# EDU_High-Speed-Design_MCU.net
KiCad netlist of a schematic drawn in Altium Designer
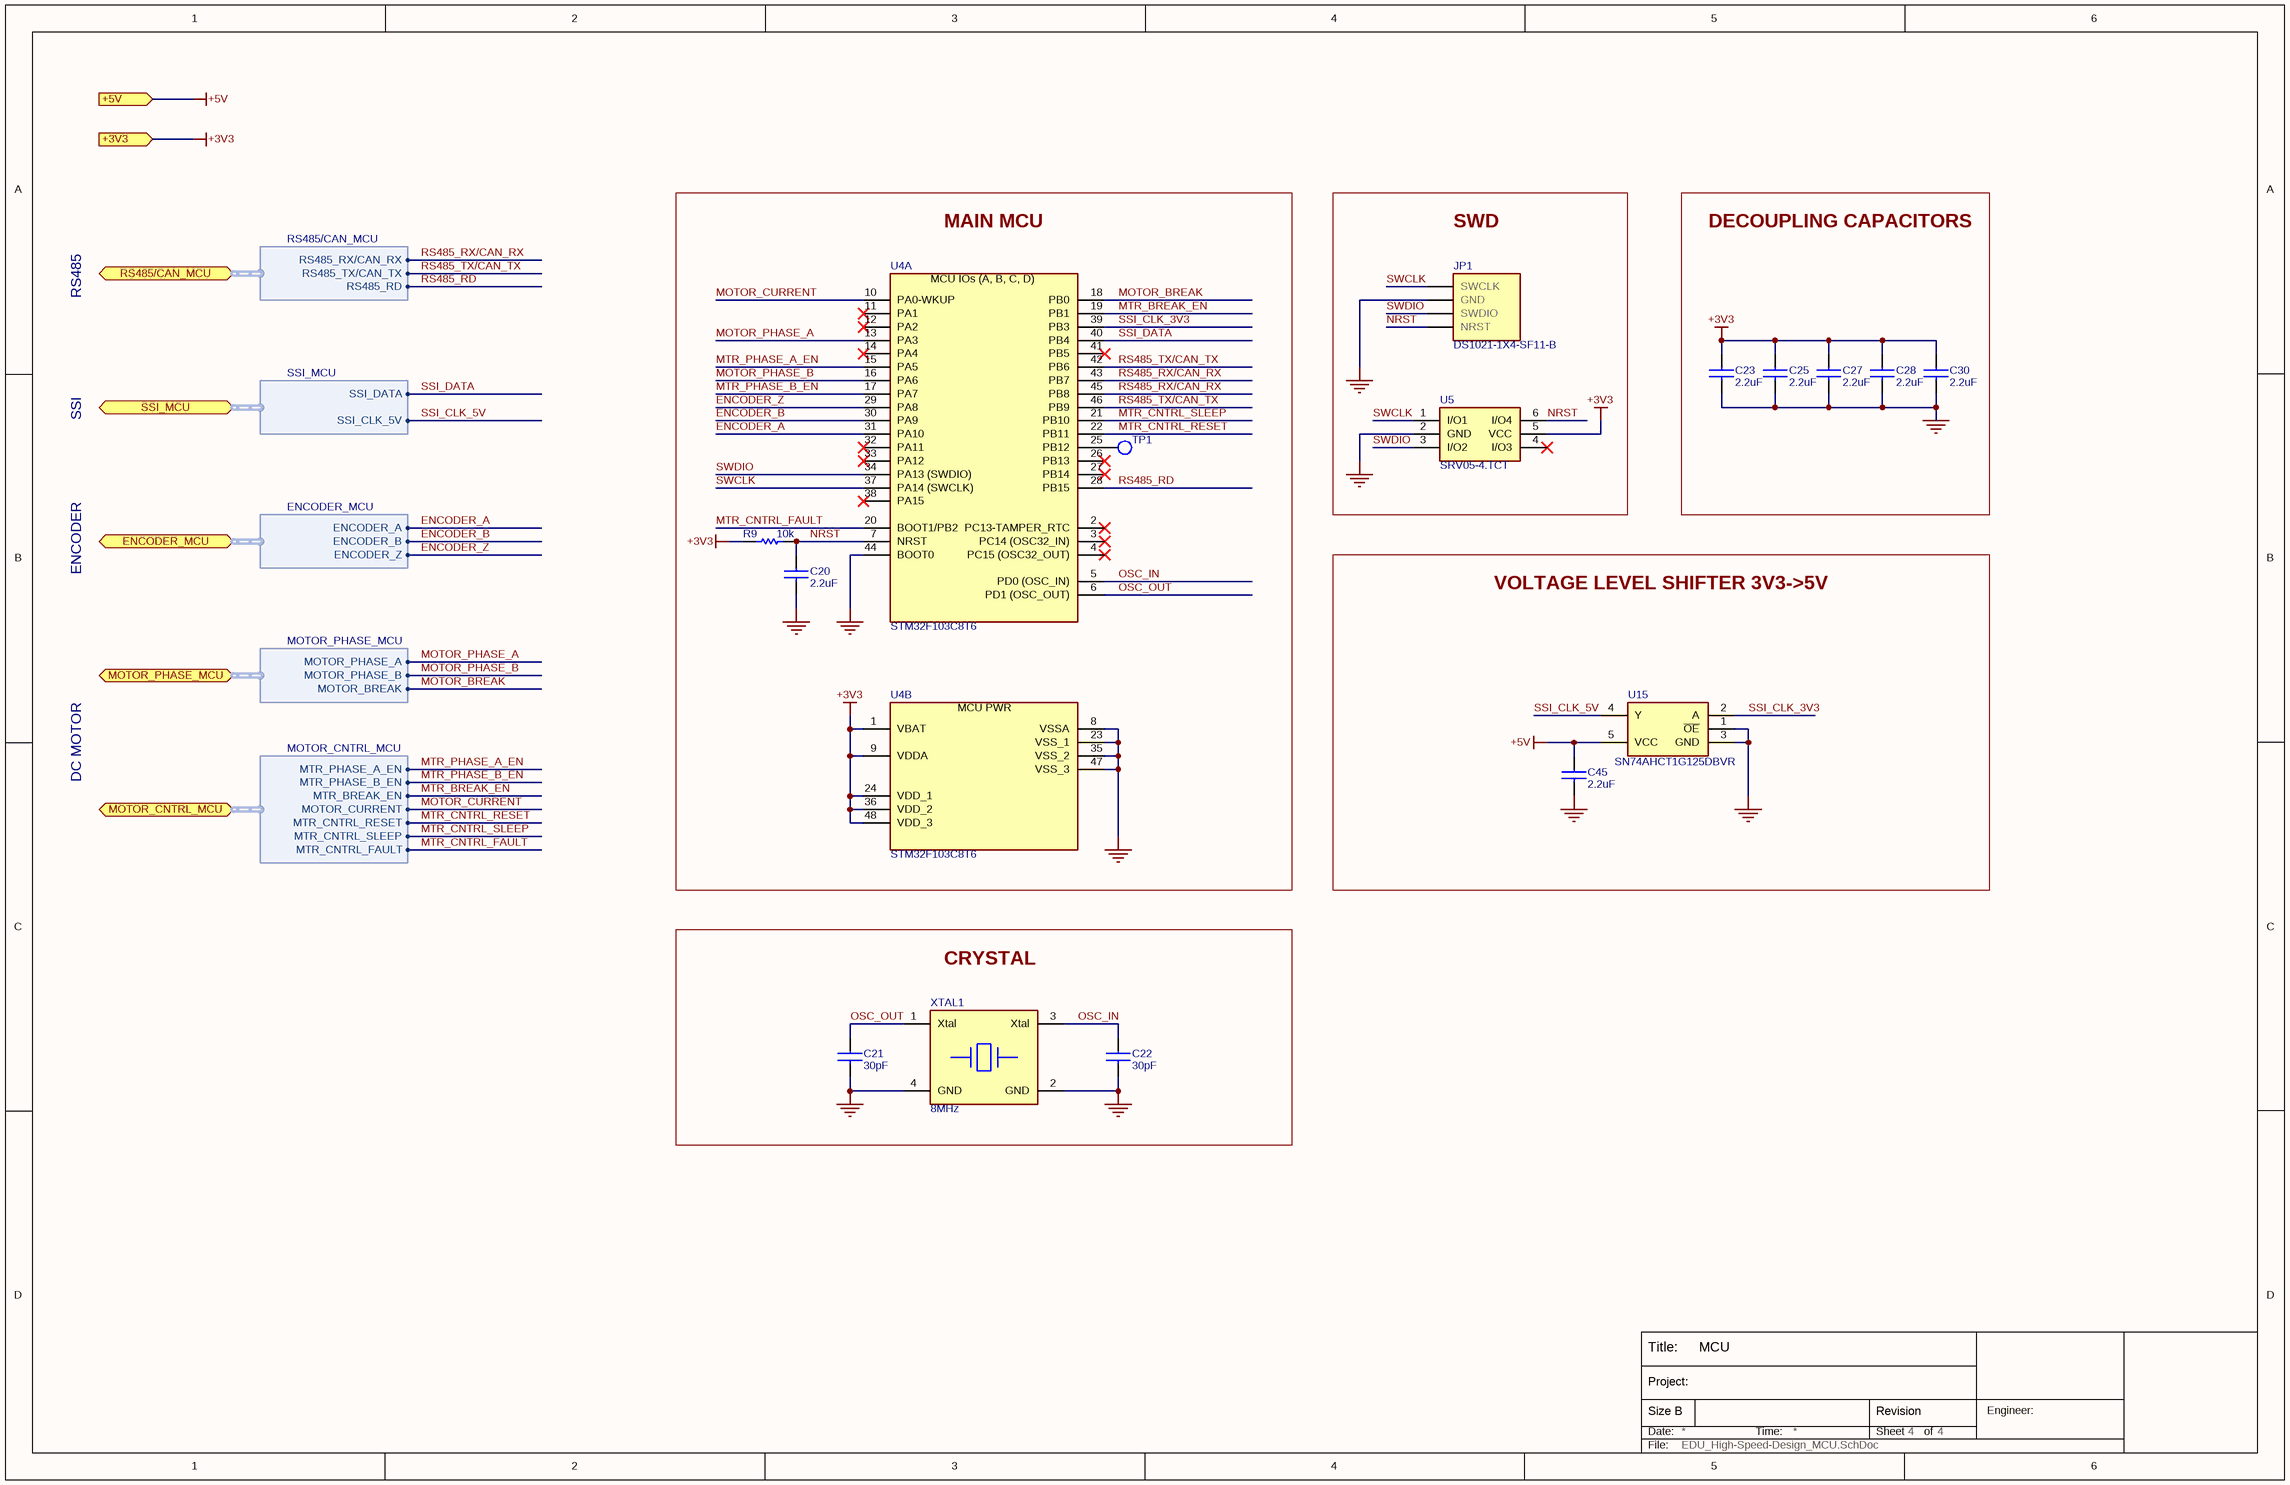
[diagram p0: EDU_High-Speed-Design_MCU.SchDoc]

(export (version "E")
  (design (tool "Eeschema 10.0.6"))
  (components
    (comp (ref "C20")
      (value "2.2uF")
      (footprint "CAP_0603")
      (description "CAP CER 2.2UF 25V X5R 0603")
      (fields (field (name "VOLTAGE") "25V"))
      (libsource (lib "ISHTAR_Robotics_dsd-outrigger-drive") (part "CC0603KRX5R8BB225"))
    )
    (comp (ref "C21")
      (value "30pF")
      (footprint "CAP_0603")
      (description "CAP CER 30PF 50V C0G/NPO 0603")
      (fields (field (name "VOLTAGE") "50V"))
      (libsource (lib "ISHTAR_Robotics_dsd-outrigger-drive") (part "CC0603JRNPO9BN300"))
    )
    (comp (ref "C22")
      (value "30pF")
      (footprint "CAP_0603")
      (description "CAP CER 30PF 50V C0G/NPO 0603")
      (fields (field (name "VOLTAGE") "50V"))
      (libsource (lib "ISHTAR_Robotics_dsd-outrigger-drive") (part "CC0603JRNPO9BN300"))
    )
    (comp (ref "C23")
      (value "2.2uF")
      (footprint "CAP_0603")
      (description "CAP CER 2.2UF 25V X5R 0603")
      (fields (field (name "VOLTAGE") "25V"))
      (libsource (lib "ISHTAR_Robotics_dsd-outrigger-drive") (part "CC0603KRX5R8BB225"))
    )
    (comp (ref "C25")
      (value "2.2uF")
      (footprint "CAP_0603")
      (description "CAP CER 2.2UF 25V X5R 0603")
      (fields (field (name "VOLTAGE") "25V"))
      (libsource (lib "ISHTAR_Robotics_dsd-outrigger-drive") (part "CC0603KRX5R8BB225"))
    )
    (comp (ref "C27")
      (value "2.2uF")
      (footprint "CAP_0603")
      (description "CAP CER 2.2UF 25V X5R 0603")
      (fields (field (name "VOLTAGE") "25V"))
      (libsource (lib "ISHTAR_Robotics_dsd-outrigger-drive") (part "CC0603KRX5R8BB225"))
    )
    (comp (ref "C28")
      (value "2.2uF")
      (footprint "CAP_0603")
      (description "CAP CER 2.2UF 25V X5R 0603")
      (fields (field (name "VOLTAGE") "25V"))
      (libsource (lib "ISHTAR_Robotics_dsd-outrigger-drive") (part "CC0603KRX5R8BB225"))
    )
    (comp (ref "C30")
      (value "2.2uF")
      (footprint "CAP_0603")
      (description "CAP CER 2.2UF 25V X5R 0603")
      (fields (field (name "VOLTAGE") "25V"))
      (libsource (lib "ISHTAR_Robotics_dsd-outrigger-drive") (part "CC0603KRX5R8BB225"))
    )
    (comp (ref "C45")
      (value "2.2uF")
      (footprint "CAP_0603")
      (description "CAP CER 2.2UF 25V X5R 0603")
      (fields (field (name "VOLTAGE") "25V"))
      (libsource (lib "ISHTAR_Robotics_dsd-outrigger-drive") (part "CC0603KRX5R8BB225"))
    )
    (comp (ref "JP1")
      (value "DS1021-1X4-SF11-B")
      (footprint "DS1021-1X4-SF11-B")
      (description "CONN HEADER VERT 4POS 2.54MM")
      (libsource (lib "ISHTAR_Robotics_dsd-outrigger-drive") (part "DS1021-1X4-SF11-B"))
    )
    (comp (ref "R9")
      (value "10k")
      (footprint "RES_0603")
      (description "RES 10K OHM 1% 1/10W 0603")
      (libsource (lib "ISHTAR_Robotics_dsd-outrigger-drive") (part "RC0603FR-0710KL"))
    )
    (comp (ref "TP1")
      (value "TEST_POINT_SMT")
      (footprint "TEST_POINT_SMT")
      (description "STM TEST POINT")
      (libsource (lib "ISHTAR_Robotics_dsd-outrigger-drive") (part "TEST_POINT_SMT"))
    )
    (comp (ref "U4")
      (value "STM32F103C8T6")
      (footprint "LQFP48")
      (description "IC MCU 32BIT 64KB FLASH 48LQFP")
      (libsource (lib "ISHTAR_Robotics_dsd-outrigger-drive") (part "STM32F103C8T6"))
    )
    (comp (ref "U5")
      (value "SRV05-4.TCT")
      (footprint "SOT-23-6")
      (description "TVS DIODE 5VWM 17.5VC SOT23-6")
      (libsource (lib "ISHTAR_Robotics_dsd-outrigger-drive") (part "SRV05-4.TCT"))
    )
    (comp (ref "U15")
      (value "SN74AHCT1G125DBVR")
      (footprint "SOT-23-5")
      (description "IC BUF NON-INVERT 5.5V SOT23-5")
      (libsource (lib "ISHTAR_Robotics_dsd-outrigger-drive") (part "SN74AHCT1G125DBVR"))
    )
    (comp (ref "XTAL1")
      (value "8MHz")
      (footprint "ABM3B-8.000MHZ-B2-T")
      (description "CRYSTAL 8.0000MHZ 18PF SMD")
      (libsource (lib "ISHTAR_Robotics_dsd-outrigger-drive") (part "ABM3B-8.000MHZ-B2-T"))
    )
  )
  (nets
    (net (code "6") (name "+3V3") (class "Default")
      (node (ref "C23") (pin "1") (pinfunction "1_1") (pintype "passive"))
      (node (ref "C25") (pin "1") (pinfunction "1_1") (pintype "passive"))
      (node (ref "C27") (pin "1") (pinfunction "1_1") (pintype "passive"))
      (node (ref "C28") (pin "1") (pinfunction "1_1") (pintype "passive"))
      (node (ref "C30") (pin "1") (pinfunction "1_1") (pintype "passive"))
      (node (ref "R9") (pin "2") (pinfunction "2_2") (pintype "passive"))
      (node (ref "U4") (pin "1") (pinfunction "VBAT_1") (pintype "passive"))
      (node (ref "U4") (pin "24") (pinfunction "VDD_1_24") (pintype "passive"))
      (node (ref "U4") (pin "36") (pinfunction "VDD_2_36") (pintype "passive"))
      (node (ref "U4") (pin "48") (pinfunction "VDD_3_48") (pintype "passive"))
      (node (ref "U4") (pin "9") (pinfunction "VDDA_9") (pintype "passive"))
      (node (ref "U5") (pin "5") (pinfunction "VCC_5") (pintype "passive"))
    )
    (net (code "7") (name "+5V") (class "Default")
      (node (ref "C45") (pin "1") (pinfunction "1_1") (pintype "passive"))
      (node (ref "U15") (pin "5") (pinfunction "VCC_5") (pintype "passive"))
    )
    (net (code "8") (name "/ENCODER_A") (class "Default")
      (node (ref "U4") (pin "31") (pinfunction "PA10_31") (pintype "passive"))
    )
    (net (code "9") (name "/ENCODER_B") (class "Default")
      (node (ref "U4") (pin "30") (pinfunction "PA9_30") (pintype "passive"))
    )
    (net (code "10") (name "/ENCODER_Z") (class "Default")
      (node (ref "U4") (pin "29") (pinfunction "PA8_29") (pintype "passive"))
    )
    (net (code "11") (name "/MOTOR_BREAK") (class "Default")
      (node (ref "U4") (pin "18") (pinfunction "PB0_18") (pintype "passive"))
    )
    (net (code "12") (name "/MOTOR_CURRENT") (class "Default")
      (node (ref "U4") (pin "10") (pinfunction "PA0-WKUP_10") (pintype "passive"))
    )
    (net (code "13") (name "/MOTOR_PHASE_A") (class "Default")
      (node (ref "U4") (pin "13") (pinfunction "PA3_13") (pintype "passive"))
    )
    (net (code "14") (name "/MOTOR_PHASE_B") (class "Default")
      (node (ref "U4") (pin "16") (pinfunction "PA6_16") (pintype "passive"))
    )
    (net (code "15") (name "/MTR_BREAK_EN") (class "Default")
      (node (ref "U4") (pin "19") (pinfunction "PB1_19") (pintype "passive"))
    )
    (net (code "16") (name "/MTR_CNTRL_FAULT") (class "Default")
      (node (ref "U4") (pin "20") (pinfunction "BOOT1/PB2_20") (pintype "passive"))
    )
    (net (code "17") (name "/MTR_CNTRL_RESET") (class "Default")
      (node (ref "U4") (pin "22") (pinfunction "PB11_22") (pintype "passive"))
    )
    (net (code "18") (name "/MTR_CNTRL_SLEEP") (class "Default")
      (node (ref "U4") (pin "21") (pinfunction "PB10_21") (pintype "passive"))
    )
    (net (code "19") (name "/MTR_PHASE_A_EN") (class "Default")
      (node (ref "U4") (pin "15") (pinfunction "PA5_15") (pintype "passive"))
    )
    (net (code "20") (name "/MTR_PHASE_B_EN") (class "Default")
      (node (ref "U4") (pin "17") (pinfunction "PA7_17") (pintype "passive"))
    )
    (net (code "21") (name "/NRST") (class "Default")
      (node (ref "C20") (pin "1") (pinfunction "1_1") (pintype "passive"))
      (node (ref "JP1") (pin "4") (pinfunction "4_4") (pintype "passive"))
      (node (ref "R9") (pin "1") (pinfunction "1_1") (pintype "passive"))
      (node (ref "U4") (pin "7") (pinfunction "NRST_7") (pintype "passive"))
      (node (ref "U5") (pin "6") (pinfunction "I/O4_6") (pintype "passive"))
    )
    (net (code "22") (name "/OSC_IN") (class "Default")
      (node (ref "C22") (pin "1") (pinfunction "1_1") (pintype "passive"))
      (node (ref "U4") (pin "5") (pinfunction "PD0_(OSC_IN)_5") (pintype "passive"))
      (node (ref "XTAL1") (pin "3") (pinfunction "Xtal_3") (pintype "passive"))
    )
    (net (code "23") (name "/OSC_OUT") (class "Default")
      (node (ref "C21") (pin "1") (pinfunction "1_1") (pintype "passive"))
      (node (ref "U4") (pin "6") (pinfunction "PD1_(OSC_OUT)_6") (pintype "passive"))
      (node (ref "XTAL1") (pin "1") (pinfunction "Xtal_1") (pintype "passive"))
    )
    (net (code "24") (name "/RS485_RD") (class "Default")
      (node (ref "U4") (pin "28") (pinfunction "PB15_28") (pintype "passive"))
    )
    (net (code "25") (name "/RS485_RX{slash}CAN_RX") (class "Default")
      (node (ref "U4") (pin "43") (pinfunction "PB7_43") (pintype "passive"))
      (node (ref "U4") (pin "45") (pinfunction "PB8_45") (pintype "passive"))
    )
    (net (code "26") (name "/RS485_TX{slash}CAN_TX") (class "Default")
      (node (ref "U4") (pin "42") (pinfunction "PB6_42") (pintype "passive"))
      (node (ref "U4") (pin "46") (pinfunction "PB9_46") (pintype "passive"))
    )
    (net (code "27") (name "/SSI_CLK_3V3") (class "Default")
      (node (ref "U15") (pin "2") (pinfunction "A_2") (pintype "passive"))
      (node (ref "U4") (pin "39") (pinfunction "PB3_39") (pintype "passive"))
    )
    (net (code "28") (name "/SSI_CLK_5V") (class "Default")
      (node (ref "U15") (pin "4") (pinfunction "Y_4") (pintype "passive"))
    )
    (net (code "29") (name "/SSI_DATA") (class "Default")
      (node (ref "U4") (pin "40") (pinfunction "PB4_40") (pintype "passive"))
    )
    (net (code "30") (name "/SWCLK") (class "Default")
      (node (ref "JP1") (pin "1") (pinfunction "1_1") (pintype "passive"))
      (node (ref "U4") (pin "37") (pinfunction "PA14_(SWCLK)_37") (pintype "passive"))
      (node (ref "U5") (pin "1") (pinfunction "I/O1_1") (pintype "passive"))
    )
    (net (code "31") (name "/SWDIO") (class "Default")
      (node (ref "JP1") (pin "3") (pinfunction "3_3") (pintype "passive"))
      (node (ref "U4") (pin "34") (pinfunction "PA13_(SWDIO)_34") (pintype "passive"))
      (node (ref "U5") (pin "3") (pinfunction "I/O2_3") (pintype "passive"))
    )
    (net (code "37") (name "GND") (class "Default")
      (node (ref "C20") (pin "2") (pinfunction "2_2") (pintype "passive"))
      (node (ref "C21") (pin "2") (pinfunction "2_2") (pintype "passive"))
      (node (ref "C22") (pin "2") (pinfunction "2_2") (pintype "passive"))
      (node (ref "C23") (pin "2") (pinfunction "2_2") (pintype "passive"))
      (node (ref "C25") (pin "2") (pinfunction "2_2") (pintype "passive"))
      (node (ref "C27") (pin "2") (pinfunction "2_2") (pintype "passive"))
      (node (ref "C28") (pin "2") (pinfunction "2_2") (pintype "passive"))
      (node (ref "C30") (pin "2") (pinfunction "2_2") (pintype "passive"))
      (node (ref "C45") (pin "2") (pinfunction "2_2") (pintype "passive"))
      (node (ref "JP1") (pin "2") (pinfunction "2_2") (pintype "passive"))
      (node (ref "U15") (pin "1") (pinfunction "~{OE}_1") (pintype "passive"))
      (node (ref "U15") (pin "3") (pinfunction "GND_3") (pintype "passive"))
      (node (ref "U4") (pin "23") (pinfunction "VSS_1_23") (pintype "passive"))
      (node (ref "U4") (pin "35") (pinfunction "VSS_2_35") (pintype "passive"))
      (node (ref "U4") (pin "44") (pinfunction "BOOT0_44") (pintype "passive"))
      (node (ref "U4") (pin "47") (pinfunction "VSS_3_47") (pintype "passive"))
      (node (ref "U4") (pin "8") (pinfunction "VSSA_8") (pintype "passive"))
      (node (ref "U5") (pin "2") (pinfunction "GND_2") (pintype "passive"))
      (node (ref "XTAL1") (pin "2") (pinfunction "GND_2") (pintype "passive"))
      (node (ref "XTAL1") (pin "4") (pinfunction "GND_4") (pintype "passive"))
    )
    (net (code "38") (name "Net-(U4A-PB12)") (class "Default")
      (node (ref "TP1") (pin "1") (pinfunction "1_1") (pintype "passive"))
      (node (ref "U4") (pin "25") (pinfunction "PB12_25") (pintype "passive"))
    )
    (net (code "39") (name "unconnected-(U4A-PA1-Pad11)") (class "Default")
      (node (ref "U4") (pin "11") (pinfunction "PA1_11") (pintype "passive+no_connect"))
    )
    (net (code "40") (name "unconnected-(U4A-PA2-Pad12)") (class "Default")
      (node (ref "U4") (pin "12") (pinfunction "PA2_12") (pintype "passive+no_connect"))
    )
    (net (code "41") (name "unconnected-(U4A-PA4-Pad14)") (class "Default")
      (node (ref "U4") (pin "14") (pinfunction "PA4_14") (pintype "passive+no_connect"))
    )
    (net (code "42") (name "unconnected-(U4A-PA11-Pad32)") (class "Default")
      (node (ref "U4") (pin "32") (pinfunction "PA11_32") (pintype "passive+no_connect"))
    )
    (net (code "43") (name "unconnected-(U4A-PA12-Pad33)") (class "Default")
      (node (ref "U4") (pin "33") (pinfunction "PA12_33") (pintype "passive+no_connect"))
    )
    (net (code "44") (name "unconnected-(U4A-PA15-Pad38)") (class "Default")
      (node (ref "U4") (pin "38") (pinfunction "PA15_38") (pintype "passive+no_connect"))
    )
    (net (code "45") (name "unconnected-(U4A-PB5-Pad41)") (class "Default")
      (node (ref "U4") (pin "41") (pinfunction "PB5_41") (pintype "passive+no_connect"))
    )
    (net (code "46") (name "unconnected-(U4A-PB13-Pad26)") (class "Default")
      (node (ref "U4") (pin "26") (pinfunction "PB13_26") (pintype "passive+no_connect"))
    )
    (net (code "47") (name "unconnected-(U4A-PB14-Pad27)") (class "Default")
      (node (ref "U4") (pin "27") (pinfunction "PB14_27") (pintype "passive+no_connect"))
    )
    (net (code "48") (name "unconnected-(U4A-PC13-TAMPER_RTC-Pad2)") (class "Default")
      (node (ref "U4") (pin "2") (pinfunction "PC13-TAMPER_RTC_2") (pintype "passive+no_connect"))
    )
    (net (code "49") (name "unconnected-(U4A-PC14_(OSC32_IN)-Pad3)") (class "Default")
      (node (ref "U4") (pin "3") (pinfunction "PC14_(OSC32_IN)_3") (pintype "passive+no_connect"))
    )
    (net (code "50") (name "unconnected-(U4A-PC15_(OSC32_OUT)-Pad4)") (class "Default")
      (node (ref "U4") (pin "4") (pinfunction "PC15_(OSC32_OUT)_4") (pintype "passive+no_connect"))
    )
    (net (code "51") (name "unconnected-(U5-I{slash}O3-Pad4)") (class "Default")
      (node (ref "U5") (pin "4") (pinfunction "I/O3_4") (pintype "passive+no_connect"))
    )
  )
)
